# MetronomeSMD.net
KiCad netlist of a schematic drawn in EAGLE
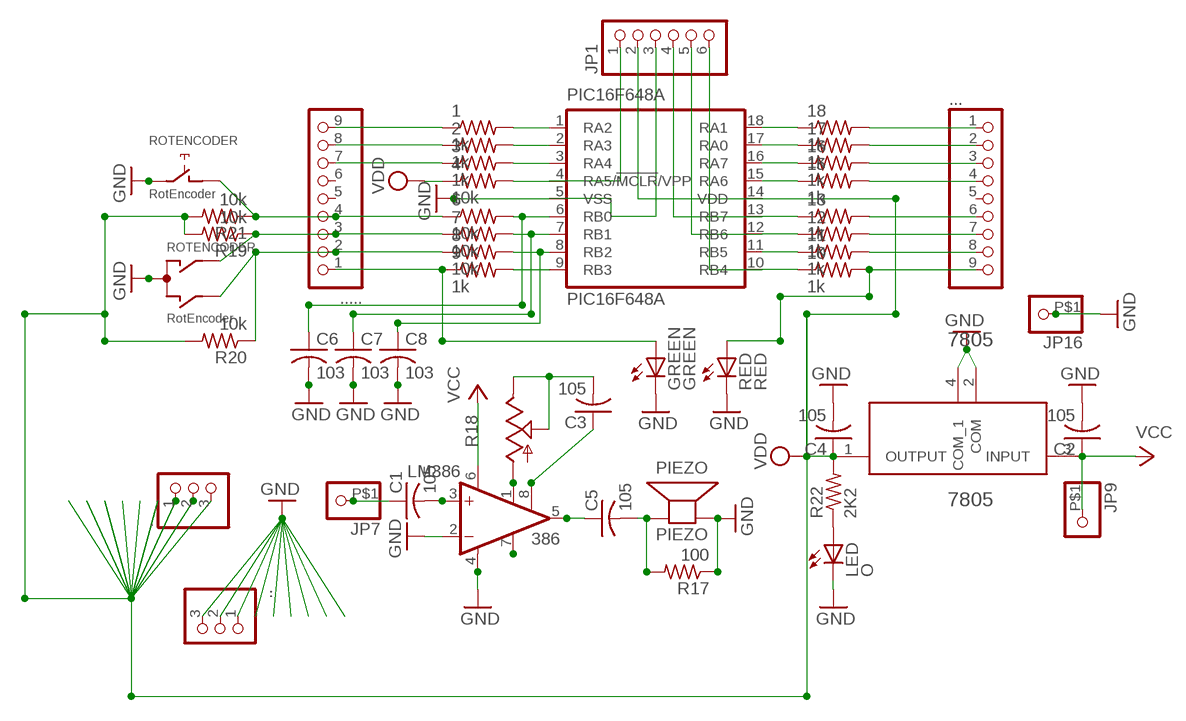
[diagram p0: schematic, sheet 1]

(export (version "E")
  (design (tool "Eeschema 10.0.6"))
  (components
    (comp (ref ".")
      (value "PINHD-1X3CB")
      (footprint "eagle-import:1X03-CLEANBIG")
      (libsource (lib "eagle-import") (part "PINHD-1X3CB"))
    )
    (comp (ref "..")
      (value "PINHD-1X3CB")
      (footprint "eagle-import:1X03-CLEANBIG")
      (libsource (lib "eagle-import") (part "PINHD-1X3CB"))
    )
    (comp (ref "...")
      (value "PINHD-1X9")
      (footprint "eagle-import:1X09-BIG")
      (libsource (lib "eagle-import") (part "PINHD-1X9"))
    )
    (comp (ref ".....")
      (value "PINHD-1X9")
      (footprint "eagle-import:1X09-BIG")
      (libsource (lib "eagle-import") (part "PINHD-1X9"))
    )
    (comp (ref "1")
      (value "1k")
      (footprint "eagle-import:R1206")
      (libsource (lib "eagle-import") (part "R-US_R1206"))
    )
    (comp (ref "2")
      (value "1k")
      (footprint "eagle-import:R1206")
      (libsource (lib "eagle-import") (part "R-US_R1206"))
    )
    (comp (ref "3")
      (value "1k")
      (footprint "eagle-import:R1206")
      (libsource (lib "eagle-import") (part "R-US_R1206"))
    )
    (comp (ref "4")
      (value "10k")
      (footprint "eagle-import:R1206")
      (libsource (lib "eagle-import") (part "R-US_R1206"))
    )
    (comp (ref "6")
      (value "10k")
      (footprint "eagle-import:R1206")
      (libsource (lib "eagle-import") (part "R-US_R1206"))
    )
    (comp (ref "7")
      (value "10k")
      (footprint "eagle-import:R1206")
      (libsource (lib "eagle-import") (part "R-US_R1206"))
    )
    (comp (ref "8")
      (value "10k")
      (footprint "eagle-import:R1206")
      (libsource (lib "eagle-import") (part "R-US_R1206"))
    )
    (comp (ref "9")
      (value "1k")
      (footprint "eagle-import:R1206")
      (libsource (lib "eagle-import") (part "R-US_R1206"))
    )
    (comp (ref "10")
      (value "1k")
      (footprint "eagle-import:R1206")
      (libsource (lib "eagle-import") (part "R-US_R1206"))
    )
    (comp (ref "11")
      (value "1k")
      (footprint "eagle-import:R1206")
      (libsource (lib "eagle-import") (part "R-US_R1206"))
    )
    (comp (ref "12")
      (value "1k")
      (footprint "eagle-import:R1206")
      (libsource (lib "eagle-import") (part "R-US_R1206"))
    )
    (comp (ref "13")
      (value "1k")
      (footprint "eagle-import:R1206")
      (libsource (lib "eagle-import") (part "R-US_R1206"))
    )
    (comp (ref "15")
      (value "1k")
      (footprint "eagle-import:R1206")
      (libsource (lib "eagle-import") (part "R-US_R1206"))
    )
    (comp (ref "16")
      (value "1k")
      (footprint "eagle-import:R1206")
      (libsource (lib "eagle-import") (part "R-US_R1206"))
    )
    (comp (ref "17")
      (value "1k")
      (footprint "eagle-import:R1206")
      (libsource (lib "eagle-import") (part "R-US_R1206"))
    )
    (comp (ref "18")
      (value "1k")
      (footprint "eagle-import:R1206")
      (libsource (lib "eagle-import") (part "R-US_R1206"))
    )
    (comp (ref "7805")
      (value "7805")
      (footprint "eagle-import:SOT150P400X160-4N")
      (fields (field (name "MPN") "UA78L05ACPKG3"))
      (libsource (lib "eagle-import") (part "UA78L05ACPKG3"))
    )
    (comp (ref "C1")
      (value "105")
      (footprint "eagle-import:C1210")
      (libsource (lib "eagle-import") (part "C-USC1210"))
    )
    (comp (ref "C2")
      (value "105")
      (footprint "eagle-import:C1210")
      (libsource (lib "eagle-import") (part "C-USC1210"))
    )
    (comp (ref "C3")
      (value "105")
      (footprint "eagle-import:C1210")
      (libsource (lib "eagle-import") (part "C-USC1210"))
    )
    (comp (ref "C4")
      (value "105")
      (footprint "eagle-import:C1210")
      (libsource (lib "eagle-import") (part "C-USC1210"))
    )
    (comp (ref "C5")
      (value "105")
      (footprint "eagle-import:C1210")
      (libsource (lib "eagle-import") (part "C-USC1210"))
    )
    (comp (ref "C6")
      (value "103")
      (footprint "eagle-import:C1210")
      (libsource (lib "eagle-import") (part "C-USC1210"))
    )
    (comp (ref "C7")
      (value "103")
      (footprint "eagle-import:C1210")
      (libsource (lib "eagle-import") (part "C-USC1210"))
    )
    (comp (ref "C8")
      (value "103")
      (footprint "eagle-import:C1210")
      (libsource (lib "eagle-import") (part "C-USC1210"))
    )
    (comp (ref "GREEN")
      (value "GREEN")
      (footprint "eagle-import:LED5MM")
      (libsource (lib "eagle-import") (part "LED5MM"))
    )
    (comp (ref "JP1")
      (value "PINHD-1X6LOCK")
      (footprint "eagle-import:1X06-BIGLOCK")
      (libsource (lib "eagle-import") (part "PINHD-1X6LOCK"))
    )
    (comp (ref "JP7")
      (value "PINHD-1X1-BIGPOGO")
      (footprint "eagle-import:1X1-BIGPOGO")
      (libsource (lib "eagle-import") (part "PINHD-1X1-BIGPOGO"))
    )
    (comp (ref "JP9")
      (value "PINHD-1X1-BIGPOGO")
      (footprint "eagle-import:1X1-BIGPOGO")
      (libsource (lib "eagle-import") (part "PINHD-1X1-BIGPOGO"))
    )
    (comp (ref "JP16")
      (value "PINHD-1X1-BIGPOGO")
      (footprint "eagle-import:1X1-BIGPOGO")
      (libsource (lib "eagle-import") (part "PINHD-1X1-BIGPOGO"))
    )
    (comp (ref "LED")
      (value "O")
      (footprint "eagle-import:CHIPLED_1206")
      (libsource (lib "eagle-import") (part "LEDCHIPLED_1206"))
    )
    (comp (ref "LM386")
      (value "386")
      (footprint "eagle-import:SO08")
      (libsource (lib "eagle-import") (part "LM386?-M1"))
    )
    (comp (ref "PIC16F648A")
      (value "PIC16F648A")
      (footprint "eagle-import:DIL18")
      (libsource (lib "eagle-import") (part "PIC16F1826/27P"))
    )
    (comp (ref "PIEZO")
      (value "PIEZO")
      (footprint "eagle-import:PS12")
      (libsource (lib "eagle-import") (part "SPEAKER/PS12"))
    )
    (comp (ref "R17")
      (value "100")
      (footprint "eagle-import:R1206")
      (libsource (lib "eagle-import") (part "R-US_R1206"))
    )
    (comp (ref "R18")
      (value "TRIM_US-RJ9W")
      (footprint "eagle-import:RJ9W")
      (libsource (lib "eagle-import") (part "TRIM_US-RJ9W"))
    )
    (comp (ref "R19")
      (value "10k")
      (footprint "eagle-import:R1206")
      (libsource (lib "eagle-import") (part "R-US_R1206"))
    )
    (comp (ref "R20")
      (value "10k")
      (footprint "eagle-import:R1206")
      (libsource (lib "eagle-import") (part "R-US_R1206"))
    )
    (comp (ref "R21")
      (value "10k")
      (footprint "eagle-import:R1206")
      (libsource (lib "eagle-import") (part "R-US_R1206"))
    )
    (comp (ref "R22")
      (value "2K2")
      (footprint "eagle-import:R1206")
      (libsource (lib "eagle-import") (part "R-US_R1206"))
    )
    (comp (ref "RED")
      (value "RED")
      (footprint "eagle-import:LED5MM")
      (libsource (lib "eagle-import") (part "LED5MM"))
    )
    (comp (ref "ROTENCODER")
      (value "RotEncoder")
      (footprint "eagle-import:ALPS_EC12E_SW")
      (fields (field (name "MPN") "EC12E2424407"))
      (libsource (lib "eagle-import") (part "EC12E_SW"))
    )
  )
  (nets
    (net (code "1") (name "GND") (class "Default")
      (node (ref "..") (pin "1") (pinfunction "1_1") (pintype "passive"))
      (node (ref "..") (pin "2") (pinfunction "2_2") (pintype "passive"))
      (node (ref "..") (pin "3") (pinfunction "3_3") (pintype "passive"))
      (node (ref "7805") (pin "2") (pinfunction "COM_2") (pintype "power_in"))
      (node (ref "7805") (pin "4") (pinfunction "COM_1_4") (pintype "power_in"))
      (node (ref "C2") (pin "2") (pinfunction "2_2") (pintype "passive"))
      (node (ref "C4") (pin "2") (pinfunction "2_2") (pintype "passive"))
      (node (ref "C6") (pin "2") (pinfunction "2_2") (pintype "passive"))
      (node (ref "C7") (pin "2") (pinfunction "2_2") (pintype "passive"))
      (node (ref "C8") (pin "2") (pinfunction "2_2") (pintype "passive"))
      (node (ref "GREEN") (pin "K") (pinfunction "C_K") (pintype "passive"))
      (node (ref "JP1") (pin "3") (pinfunction "3_3") (pintype "passive"))
      (node (ref "JP16") (pin "P$1") (pinfunction "1_P$1") (pintype "passive"))
      (node (ref "LED") (pin "C") (pinfunction "C_C") (pintype "passive"))
      (node (ref "LM386") (pin "2") (pinfunction "-IN_2") (pintype "input"))
      (node (ref "LM386") (pin "4") (pinfunction "GND_4") (pintype "power_in"))
      (node (ref "PIC16F648A") (pin "5") (pinfunction "VSS_5") (pintype "power_in"))
      (node (ref "PIEZO") (pin "P$2") (pinfunction "-_P$2") (pintype "passive"))
      (node (ref "R17") (pin "1") (pinfunction "1_1") (pintype "passive"))
      (node (ref "RED") (pin "K") (pinfunction "C_K") (pintype "passive"))
      (node (ref "ROTENCODER") (pin "C") (pinfunction "C_C") (pintype "passive"))
      (node (ref "ROTENCODER") (pin "E") (pinfunction "2_E") (pintype "passive"))
    )
    (net (code "2") (name "Net-(...-Pad1)") (class "Default")
      (node (ref "...") (pin "1") (pinfunction "1_1") (pintype "passive"))
      (node (ref "18") (pin "2") (pinfunction "2_2") (pintype "passive"))
    )
    (net (code "3") (name "Net-(...-Pad2)") (class "Default")
      (node (ref "...") (pin "2") (pinfunction "2_2") (pintype "passive"))
      (node (ref "17") (pin "2") (pinfunction "2_2") (pintype "passive"))
    )
    (net (code "4") (name "Net-(...-Pad3)") (class "Default")
      (node (ref "...") (pin "3") (pinfunction "3_3") (pintype "passive"))
      (node (ref "16") (pin "2") (pinfunction "2_2") (pintype "passive"))
    )
    (net (code "5") (name "Net-(...-Pad4)") (class "Default")
      (node (ref "...") (pin "4") (pinfunction "4_4") (pintype "passive"))
      (node (ref "15") (pin "2") (pinfunction "2_2") (pintype "passive"))
    )
    (net (code "6") (name "Net-(...-Pad6)") (class "Default")
      (node (ref "...") (pin "6") (pinfunction "6_6") (pintype "passive"))
      (node (ref "13") (pin "2") (pinfunction "2_2") (pintype "passive"))
    )
    (net (code "7") (name "Net-(...-Pad7)") (class "Default")
      (node (ref "...") (pin "7") (pinfunction "7_7") (pintype "passive"))
      (node (ref "12") (pin "2") (pinfunction "2_2") (pintype "passive"))
    )
    (net (code "8") (name "Net-(...-Pad8)") (class "Default")
      (node (ref "...") (pin "8") (pinfunction "8_8") (pintype "passive"))
      (node (ref "11") (pin "2") (pinfunction "2_2") (pintype "passive"))
    )
    (net (code "9") (name "Net-(...-Pad9)") (class "Default")
      (node (ref "...") (pin "9") (pinfunction "9_9") (pintype "passive"))
      (node (ref "10") (pin "2") (pinfunction "2_2") (pintype "passive"))
      (node (ref "RED") (pin "A") (pinfunction "A_A") (pintype "passive"))
    )
    (net (code "10") (name "Net-(.....-Pad1)") (class "Default")
      (node (ref ".....") (pin "1") (pinfunction "1_1") (pintype "passive"))
      (node (ref "9") (pin "1") (pinfunction "1_1") (pintype "passive"))
      (node (ref "GREEN") (pin "A") (pinfunction "A_A") (pintype "passive"))
    )
    (net (code "11") (name "Net-(.....-Pad2)") (class "Default")
      (node (ref ".....") (pin "2") (pinfunction "2_2") (pintype "passive"))
      (node (ref "8") (pin "1") (pinfunction "1_1") (pintype "passive"))
      (node (ref "R20") (pin "1") (pinfunction "1_1") (pintype "passive"))
      (node (ref "ROTENCODER") (pin "B") (pinfunction "B_B") (pintype "passive"))
    )
    (net (code "12") (name "Net-(.....-Pad3)") (class "Default")
      (node (ref ".....") (pin "3") (pinfunction "3_3") (pintype "passive"))
      (node (ref "7") (pin "1") (pinfunction "1_1") (pintype "passive"))
      (node (ref "R19") (pin "1") (pinfunction "1_1") (pintype "passive"))
      (node (ref "ROTENCODER") (pin "A") (pinfunction "A_A") (pintype "passive"))
    )
    (net (code "13") (name "Net-(.....-Pad7)") (class "Default")
      (node (ref ".....") (pin "7") (pinfunction "7_7") (pintype "passive"))
      (node (ref "3") (pin "1") (pinfunction "1_1") (pintype "passive"))
    )
    (net (code "14") (name "Net-(.....-Pad8)") (class "Default")
      (node (ref ".....") (pin "8") (pinfunction "8_8") (pintype "passive"))
      (node (ref "2") (pin "1") (pinfunction "1_1") (pintype "passive"))
    )
    (net (code "15") (name "Net-(.....-Pad9)") (class "Default")
      (node (ref ".....") (pin "9") (pinfunction "9_9") (pintype "passive"))
      (node (ref "1") (pin "1") (pinfunction "1_1") (pintype "passive"))
    )
    (net (code "16") (name "Net-(C3-Pad1)") (class "Default")
      (node (ref "C3") (pin "1") (pinfunction "1_1") (pintype "passive"))
      (node (ref "LM386") (pin "8") (pinfunction "GAIN_8") (pintype "passive"))
    )
    (net (code "17") (name "Net-(C3-Pad2)") (class "Default")
      (node (ref "C3") (pin "2") (pinfunction "2_2") (pintype "passive"))
      (node (ref "R18") (pin "E") (pinfunction "E_E") (pintype "passive"))
      (node (ref "R18") (pin "S") (pinfunction "S_S") (pintype "passive"))
    )
    (net (code "18") (name "Net-(JP7-1)") (class "Default")
      (node (ref "C1") (pin "1") (pinfunction "1_1") (pintype "passive"))
      (node (ref "JP7") (pin "P$1") (pinfunction "1_P$1") (pintype "passive"))
    )
    (net (code "19") (name "Net-(LED-PadA)") (class "Default")
      (node (ref "LED") (pin "A") (pinfunction "A_A") (pintype "passive"))
      (node (ref "R22") (pin "1") (pinfunction "1_1") (pintype "passive"))
    )
    (net (code "20") (name "Net-(LM386-+IN)") (class "Default")
      (node (ref "C1") (pin "2") (pinfunction "2_2") (pintype "passive"))
      (node (ref "LM386") (pin "3") (pinfunction "+IN_3") (pintype "input"))
    )
    (net (code "21") (name "Net-(LM386-GAIN-Pad1)") (class "Default")
      (node (ref "LM386") (pin "1") (pinfunction "GAIN_1") (pintype "passive"))
      (node (ref "R18") (pin "A") (pinfunction "A_A") (pintype "passive"))
    )
    (net (code "22") (name "Net-(LM386-OUT)") (class "Default")
      (node (ref "C5") (pin "1") (pinfunction "1_1") (pintype "passive"))
      (node (ref "LM386") (pin "5") (pinfunction "OUT_5") (pintype "output"))
    )
    (net (code "23") (name "Net-(PIC16F648A-RA0)") (class "Default")
      (node (ref "17") (pin "1") (pinfunction "1_1") (pintype "passive"))
      (node (ref "PIC16F648A") (pin "17") (pinfunction "RA0_17") (pintype "bidirectional"))
    )
    (net (code "24") (name "Net-(PIC16F648A-RA1)") (class "Default")
      (node (ref "18") (pin "1") (pinfunction "1_1") (pintype "passive"))
      (node (ref "PIC16F648A") (pin "18") (pinfunction "RA1_18") (pintype "bidirectional"))
    )
    (net (code "25") (name "Net-(PIC16F648A-RA2)") (class "Default")
      (node (ref "1") (pin "2") (pinfunction "2_2") (pintype "passive"))
      (node (ref "PIC16F648A") (pin "1") (pinfunction "RA2_1") (pintype "bidirectional"))
    )
    (net (code "26") (name "Net-(PIC16F648A-RA3)") (class "Default")
      (node (ref "2") (pin "2") (pinfunction "2_2") (pintype "passive"))
      (node (ref "PIC16F648A") (pin "2") (pinfunction "RA3_2") (pintype "bidirectional"))
    )
    (net (code "27") (name "Net-(PIC16F648A-RA4)") (class "Default")
      (node (ref "3") (pin "2") (pinfunction "2_2") (pintype "passive"))
      (node (ref "PIC16F648A") (pin "3") (pinfunction "RA4_3") (pintype "bidirectional"))
    )
    (net (code "28") (name "Net-(PIC16F648A-RA5{slash}~{MCLR}{slash}VPP)") (class "Default")
      (node (ref "4") (pin "2") (pinfunction "2_2") (pintype "passive"))
      (node (ref "JP1") (pin "1") (pinfunction "1_1") (pintype "passive"))
      (node (ref "PIC16F648A") (pin "4") (pinfunction "RA5/~{MCLR}/VPP_4") (pintype "bidirectional"))
    )
    (net (code "29") (name "Net-(PIC16F648A-RA6)") (class "Default")
      (node (ref "15") (pin "1") (pinfunction "1_1") (pintype "passive"))
      (node (ref "PIC16F648A") (pin "15") (pinfunction "RA6_15") (pintype "bidirectional"))
    )
    (net (code "30") (name "Net-(PIC16F648A-RA7)") (class "Default")
      (node (ref "16") (pin "1") (pinfunction "1_1") (pintype "passive"))
      (node (ref "PIC16F648A") (pin "16") (pinfunction "RA7_16") (pintype "bidirectional"))
    )
    (net (code "31") (name "Net-(PIC16F648A-RB0)") (class "Default")
      (node (ref "6") (pin "2") (pinfunction "2_2") (pintype "passive"))
      (node (ref "C6") (pin "1") (pinfunction "1_1") (pintype "passive"))
      (node (ref "PIC16F648A") (pin "6") (pinfunction "RB0_6") (pintype "bidirectional"))
    )
    (net (code "32") (name "Net-(PIC16F648A-RB1)") (class "Default")
      (node (ref "7") (pin "2") (pinfunction "2_2") (pintype "passive"))
      (node (ref "C7") (pin "1") (pinfunction "1_1") (pintype "passive"))
      (node (ref "PIC16F648A") (pin "7") (pinfunction "RB1_7") (pintype "bidirectional"))
    )
    (net (code "33") (name "Net-(PIC16F648A-RB2)") (class "Default")
      (node (ref "8") (pin "2") (pinfunction "2_2") (pintype "passive"))
      (node (ref "C8") (pin "1") (pinfunction "1_1") (pintype "passive"))
      (node (ref "PIC16F648A") (pin "8") (pinfunction "RB2_8") (pintype "bidirectional"))
    )
    (net (code "34") (name "Net-(PIC16F648A-RB3)") (class "Default")
      (node (ref "9") (pin "2") (pinfunction "2_2") (pintype "passive"))
      (node (ref "PIC16F648A") (pin "9") (pinfunction "RB3_9") (pintype "bidirectional"))
    )
    (net (code "35") (name "Net-(PIC16F648A-RB4)") (class "Default")
      (node (ref "10") (pin "1") (pinfunction "1_1") (pintype "passive"))
      (node (ref "JP1") (pin "6") (pinfunction "6_6") (pintype "passive"))
      (node (ref "PIC16F648A") (pin "10") (pinfunction "RB4_10") (pintype "bidirectional"))
    )
    (net (code "36") (name "Net-(PIC16F648A-RB5)") (class "Default")
      (node (ref "11") (pin "1") (pinfunction "1_1") (pintype "passive"))
      (node (ref "PIC16F648A") (pin "11") (pinfunction "RB5_11") (pintype "bidirectional"))
    )
    (net (code "37") (name "Net-(PIC16F648A-RB6)") (class "Default")
      (node (ref "12") (pin "1") (pinfunction "1_1") (pintype "passive"))
      (node (ref "JP1") (pin "5") (pinfunction "5_5") (pintype "passive"))
      (node (ref "PIC16F648A") (pin "12") (pinfunction "RB6_12") (pintype "bidirectional"))
    )
    (net (code "38") (name "Net-(PIC16F648A-RB7)") (class "Default")
      (node (ref "13") (pin "1") (pinfunction "1_1") (pintype "passive"))
      (node (ref "JP1") (pin "4") (pinfunction "4_4") (pintype "passive"))
      (node (ref "PIC16F648A") (pin "13") (pinfunction "RB7_13") (pintype "bidirectional"))
    )
    (net (code "39") (name "Net-(PIEZO-+)") (class "Default")
      (node (ref "C5") (pin "2") (pinfunction "2_2") (pintype "passive"))
      (node (ref "PIEZO") (pin "P$1") (pinfunction "+_P$1") (pintype "passive"))
      (node (ref "R17") (pin "2") (pinfunction "2_2") (pintype "passive"))
    )
    (net (code "40") (name "Net-(ROTENCODERB-1)") (class "Default")
      (node (ref ".....") (pin "4") (pinfunction "4_4") (pintype "passive"))
      (node (ref "6") (pin "1") (pinfunction "1_1") (pintype "passive"))
      (node (ref "R21") (pin "1") (pinfunction "1_1") (pintype "passive"))
      (node (ref "ROTENCODER") (pin "D") (pinfunction "1_D") (pintype "passive"))
    )
    (net (code "41") (name "VCC") (class "Default")
      (node (ref "7805") (pin "3") (pinfunction "INPUT_3") (pintype "input"))
      (node (ref "C2") (pin "1") (pinfunction "1_1") (pintype "passive"))
      (node (ref "JP9") (pin "P$1") (pinfunction "1_P$1") (pintype "passive"))
      (node (ref "LM386") (pin "6") (pinfunction "VS_6") (pintype "power_in"))
    )
    (net (code "42") (name "VDD") (class "Default")
      (node (ref ".") (pin "1") (pinfunction "1_1") (pintype "passive"))
      (node (ref ".") (pin "2") (pinfunction "2_2") (pintype "passive"))
      (node (ref ".") (pin "3") (pinfunction "3_3") (pintype "passive"))
      (node (ref "4") (pin "1") (pinfunction "1_1") (pintype "passive"))
      (node (ref "7805") (pin "1") (pinfunction "OUTPUT_1") (pintype "output"))
      (node (ref "C4") (pin "1") (pinfunction "1_1") (pintype "passive"))
      (node (ref "JP1") (pin "2") (pinfunction "2_2") (pintype "passive"))
      (node (ref "PIC16F648A") (pin "14") (pinfunction "VDD_14") (pintype "power_in"))
      (node (ref "R19") (pin "2") (pinfunction "2_2") (pintype "passive"))
      (node (ref "R20") (pin "2") (pinfunction "2_2") (pintype "passive"))
      (node (ref "R21") (pin "2") (pinfunction "2_2") (pintype "passive"))
      (node (ref "R22") (pin "2") (pinfunction "2_2") (pintype "passive"))
    )
    (net (code "43") (name "unconnected-(...-Pad5)") (class "Default")
      (node (ref "...") (pin "5") (pinfunction "5_5") (pintype "passive"))
    )
    (net (code "44") (name "unconnected-(.....-Pad5)") (class "Default")
      (node (ref ".....") (pin "5") (pinfunction "5_5") (pintype "passive"))
    )
    (net (code "45") (name "unconnected-(.....-Pad6)") (class "Default")
      (node (ref ".....") (pin "6") (pinfunction "6_6") (pintype "passive"))
    )
    (net (code "46") (name "unconnected-(LM386-BYPASS-Pad7)") (class "Default")
      (node (ref "LM386") (pin "7") (pinfunction "BYPASS_7") (pintype "passive"))
    )
  )
)
